# LightOnOff.net
KiCad netlist of a schematic drawn in Altium Designer
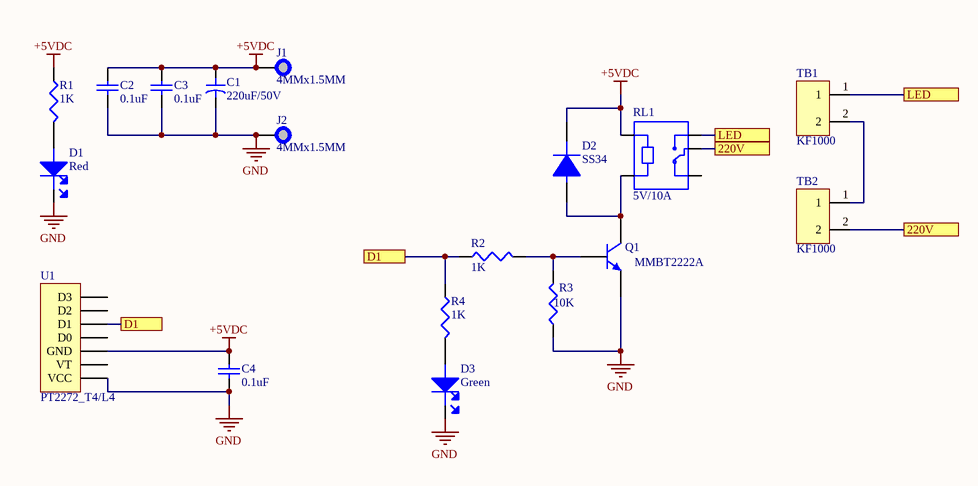
[diagram p0: LightOnOff.SchDoc]

(export (version "E")
  (design (tool "Eeschema 10.0.6"))
  (components
    (comp (ref "C1")
      (value "220uF/50V")
      (footprint "CAP_RADIAL_8MM")
      (fields
        (field (name "MANUFACTURER") "Panasonic")
        (field (name "MANUFACTURER PART NUMBER") "EEUFM1V221L")
        (field (name "TOLERANCE") "20%")
      )
      (libsource (lib "ThangTM_Sch") (part "C220uF_RADIAL_50V_8MM"))
    )
    (comp (ref "C2")
      (value "0.1uF")
      (footprint "C0805")
      (description "KEMET         C0805C104Z5VACTU.             CERAMIC CAPACITOR, 0.1UF, 50V, Y5V, +80,-20%, 0805")
      (fields
        (field (name "MANUFACTURER") "KEMET")
        (field (name "MANUFACTURER PART NUMBER") "C0805C104Z5VACTU")
      )
      (libsource (lib "ThangTM_Sch") (part "C0.1uF_0805"))
    )
    (comp (ref "C3")
      (value "0.1uF")
      (footprint "C0805")
      (description "KEMET         C0805C104Z5VACTU.             CERAMIC CAPACITOR, 0.1UF, 50V, Y5V, +80,-20%, 0805")
      (fields
        (field (name "MANUFACTURER") "KEMET")
        (field (name "MANUFACTURER PART NUMBER") "C0805C104Z5VACTU")
      )
      (libsource (lib "ThangTM_Sch") (part "C0.1uF_0805"))
    )
    (comp (ref "C4")
      (value "0.1uF")
      (footprint "C0805")
      (description "KEMET         C0805C104Z5VACTU.             CERAMIC CAPACITOR, 0.1UF, 50V, Y5V, +80,-20%, 0805")
      (fields
        (field (name "MANUFACTURER") "KEMET")
        (field (name "MANUFACTURER PART NUMBER") "C0805C104Z5VACTU")
      )
      (libsource (lib "ThangTM_Sch") (part "C0.1uF_0805"))
    )
    (comp (ref "D1")
      (value "Red")
      (footprint "LED_RED_0805")
      (description "LED RED DIFFUSED 0805 SMD")
      (fields
        (field (name "MANUFACTURER") "Osram Opto")
        (field (name "MANUFACTURER PART NUMBER") "LHR974-LP-1")
      )
      (libsource (lib "ThangTM_Sch") (part "LED_RED_0805"))
    )
    (comp (ref "D2")
      (value "SS34")
      (footprint "DO14AC SMA")
      (libsource (lib "ThangTM_Sch") (part "SS34_DO214AC"))
    )
    (comp (ref "D3")
      (value "Green")
      (footprint "LED_GREEN_0805")
      (description "Green 0805 130 º Min 5 mcd Typical 12 mcd Water Clear Lens SMT LED")
      (fields
        (field (name "MANUFACTURER") "Vishay Lite-On")
        (field (name "MANUFACTURER PART NUMBER") "LTST-C171GKT")
      )
      (libsource (lib "ThangTM_Sch") (part "LED_GREEN_0805"))
    )
    (comp (ref "J1")
      (value "4MMx1.5MM")
      (footprint "PAD_WITH_HOLE_4MMx1.5MM")
      (description "Pad with a hole 4mm x 1.5mm")
      (libsource (lib "ThangTM_Sch") (part "PAD_WITH_HOLE_4MMx1.5MM"))
    )
    (comp (ref "J2")
      (value "4MMx1.5MM")
      (footprint "PAD_WITH_HOLE_4MMx1.5MM")
      (description "Pad with a hole 4mm x 1.5mm")
      (libsource (lib "ThangTM_Sch") (part "PAD_WITH_HOLE_4MMx1.5MM"))
    )
    (comp (ref "Q1")
      (value "MMBT2222A")
      (footprint "SOT_23")
      (description "Transistors Bipolar - BJT SOT-23 NPN GEN PUR")
      (fields (field (name "BSH PART NUMBER") "Q-MMBT2222A"))
      (libsource (lib "ThangTM_Sch") (part "MMBT2222A"))
    )
    (comp (ref "R1")
      (value "1K")
      (footprint "R0805")
      (description "RES SMD 1K OHM 1% 1/8W 0805")
      (fields
        (field (name "MANUFACTURER") "Yageo")
        (field (name "MANUFACTURER PART NUMBER") "RC0805FR-071KL")
      )
      (libsource (lib "ThangTM_Sch") (part "R1K_0805"))
    )
    (comp (ref "R2")
      (value "1K")
      (footprint "R0805")
      (description "RES SMD 1K OHM 1% 1/8W 0805")
      (fields
        (field (name "MANUFACTURER") "Yageo")
        (field (name "MANUFACTURER PART NUMBER") "RC0805FR-071KL")
      )
      (libsource (lib "ThangTM_Sch") (part "R1K_0805"))
    )
    (comp (ref "R3")
      (value "10K")
      (footprint "R0805")
      (description "RES SMD 10K OHM 1% 1/8W 0805")
      (fields
        (field (name "MANUFACTURER") "Yageo")
        (field (name "MANUFACTURER PART NUMBER") "RC0805FR-0710KL")
      )
      (libsource (lib "ThangTM_Sch") (part "R10K_0805"))
    )
    (comp (ref "R4")
      (value "1K")
      (footprint "R0805")
      (description "RES SMD 1K OHM 1% 1/8W 0805")
      (fields
        (field (name "MANUFACTURER") "Yageo")
        (field (name "MANUFACTURER PART NUMBER") "RC0805FR-071KL")
      )
      (libsource (lib "ThangTM_Sch") (part "R1K_0805"))
    )
    (comp (ref "RL1")
      (value "5V/10A")
      (footprint "Relay_SRD")
      (libsource (lib "ThangTM_Sch") (part "Relay_SRD_5VDC"))
    )
    (comp (ref "TB1")
      (value "KF1000")
      (footprint "KF1000_2P")
      (libsource (lib "ThangTM_Sch") (part "KF1000_2P"))
    )
    (comp (ref "TB2")
      (value "KF1000")
      (footprint "KF1000_2P")
      (libsource (lib "ThangTM_Sch") (part "KF1000_2P"))
    )
    (comp (ref "U1")
      (value "PT2272_T4/L4")
      (footprint "PT2272_T4/L4")
      (libsource (lib "ThangTM_Sch") (part "PT2272_Module_T4/L4"))
    )
  )
  (nets
    (net (code "1") (name "+5VDC") (class "Default")
      (node (ref "C1") (pin "1") (pinfunction "1_1") (pintype "passive"))
      (node (ref "C2") (pin "2") (pinfunction "2_2") (pintype "passive"))
      (node (ref "C3") (pin "2") (pinfunction "2_2") (pintype "passive"))
      (node (ref "C4") (pin "2") (pinfunction "2_2") (pintype "passive"))
      (node (ref "D2") (pin "2") (pinfunction "Cathode_2") (pintype "passive"))
      (node (ref "J1") (pin "1") (pinfunction "1_1") (pintype "passive"))
      (node (ref "R1") (pin "1") (pinfunction "1_1") (pintype "passive"))
      (node (ref "RL1") (pin "A1") (pinfunction "A1_A1") (pintype "passive"))
      (node (ref "U1") (pin "5") (pinfunction "GND_5") (pintype "passive"))
    )
    (net (code "2") (name "/220V") (class "Default")
      (node (ref "RL1") (pin "COM") (pinfunction "COM_COM") (pintype "passive"))
      (node (ref "TB2") (pin "2") (pinfunction "2_2") (pintype "passive"))
    )
    (net (code "3") (name "/D1") (class "Default")
      (node (ref "R2") (pin "1") (pinfunction "1_1") (pintype "passive"))
      (node (ref "R4") (pin "1") (pinfunction "1_1") (pintype "passive"))
      (node (ref "U1") (pin "3") (pinfunction "D1_3") (pintype "passive"))
    )
    (net (code "4") (name "/LED") (class "Default")
      (node (ref "RL1") (pin "NO") (pinfunction "NO_NO") (pintype "passive"))
      (node (ref "TB1") (pin "1") (pinfunction "1_1") (pintype "passive"))
    )
    (net (code "5") (name "GND") (class "Default")
      (node (ref "C1") (pin "2") (pinfunction "2_2") (pintype "passive"))
      (node (ref "C2") (pin "1") (pinfunction "1_1") (pintype "passive"))
      (node (ref "C3") (pin "1") (pinfunction "1_1") (pintype "passive"))
      (node (ref "C4") (pin "1") (pinfunction "1_1") (pintype "passive"))
      (node (ref "D1") (pin "2") (pinfunction "Cathode_2") (pintype "passive"))
      (node (ref "D3") (pin "2") (pinfunction "Cathode_2") (pintype "passive"))
      (node (ref "J2") (pin "1") (pinfunction "1_1") (pintype "passive"))
      (node (ref "Q1") (pin "3") (pinfunction "E_3") (pintype "passive"))
      (node (ref "R3") (pin "1") (pinfunction "1_1") (pintype "passive"))
      (node (ref "U1") (pin "7") (pinfunction "VCC_7") (pintype "passive"))
    )
    (net (code "6") (name "Net-(D1-Anode)") (class "Default")
      (node (ref "D1") (pin "1") (pinfunction "Anode_1") (pintype "passive"))
      (node (ref "R1") (pin "2") (pinfunction "2_2") (pintype "passive"))
    )
    (net (code "7") (name "Net-(D2-Anode)") (class "Default")
      (node (ref "D2") (pin "1") (pinfunction "Anode_1") (pintype "passive"))
      (node (ref "Q1") (pin "2") (pinfunction "C_2") (pintype "passive"))
      (node (ref "RL1") (pin "A2") (pinfunction "A2_A2") (pintype "passive"))
    )
    (net (code "8") (name "Net-(D3-Anode)") (class "Default")
      (node (ref "D3") (pin "1") (pinfunction "Anode_1") (pintype "passive"))
      (node (ref "R4") (pin "2") (pinfunction "2_2") (pintype "passive"))
    )
    (net (code "9") (name "Net-(Q1-B)") (class "Default")
      (node (ref "Q1") (pin "1") (pinfunction "B_1") (pintype "passive"))
      (node (ref "R2") (pin "2") (pinfunction "2_2") (pintype "passive"))
      (node (ref "R3") (pin "2") (pinfunction "2_2") (pintype "passive"))
    )
    (net (code "10") (name "Net-(TB1-Pad2)") (class "Default")
      (node (ref "TB1") (pin "2") (pinfunction "2_2") (pintype "passive"))
      (node (ref "TB2") (pin "1") (pinfunction "1_1") (pintype "passive"))
    )
    (net (code "11") (name "unconnected-(RL1-PadNC)") (class "Default")
      (node (ref "RL1") (pin "NC") (pinfunction "NC_NC") (pintype "passive"))
    )
    (net (code "12") (name "unconnected-(U1-D0-Pad4)") (class "Default")
      (node (ref "U1") (pin "4") (pinfunction "D0_4") (pintype "passive"))
    )
    (net (code "13") (name "unconnected-(U1-D2-Pad2)") (class "Default")
      (node (ref "U1") (pin "2") (pinfunction "D2_2") (pintype "passive"))
    )
    (net (code "14") (name "unconnected-(U1-D3-Pad1)") (class "Default")
      (node (ref "U1") (pin "1") (pinfunction "D3_1") (pintype "passive"))
    )
    (net (code "15") (name "unconnected-(U1-VT-Pad6)") (class "Default")
      (node (ref "U1") (pin "6") (pinfunction "VT_6") (pintype "passive"))
    )
  )
)
